# 7_Peripherals.net
KiCad netlist of a schematic drawn in Altium Designer
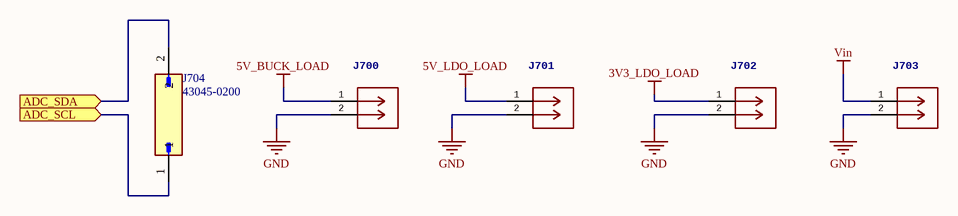
[diagram p0: 7_Peripherals.SchDoc]

(export (version "E")
  (design (tool "Eeschema 10.0.6"))
  (components
    (comp (ref "J700")
      (value "05325-90229")
      (footprint "MOLEX_532590229")
      (description "Molex Mighty-SPOX 2POS")
      (fields (field (name "MANUFACTURER") "Molex") (field (name "PARTNUMBER") "532590229"))
      (libsource (lib "Connectors") (part "0532590229"))
    )
    (comp (ref "J701")
      (value "05325-90229")
      (footprint "MOLEX_532590229")
      (description "Molex Mighty-SPOX 2POS")
      (fields (field (name "MANUFACTURER") "Molex") (field (name "PARTNUMBER") "532590229"))
      (libsource (lib "Connectors") (part "0532590229"))
    )
    (comp (ref "J702")
      (value "05325-90229")
      (footprint "MOLEX_532590229")
      (description "Molex Mighty-SPOX 2POS")
      (fields (field (name "MANUFACTURER") "Molex") (field (name "PARTNUMBER") "532590229"))
      (libsource (lib "Connectors") (part "0532590229"))
    )
    (comp (ref "J703")
      (value "05325-90229")
      (footprint "MOLEX_532590229")
      (description "Molex Mighty-SPOX 2POS")
      (fields (field (name "MANUFACTURER") "Molex") (field (name "PARTNUMBER") "532590229"))
      (libsource (lib "Connectors") (part "0532590229"))
    )
    (comp (ref "J704")
      (value "43045-0200")
      (footprint "MOLEX_43045-0200")
      (description "Molex Microfit 2POS")
      (fields (field (name "MF") "Molex") (field (name "DIGI-KEY_PART_NUMBER") "WM1813-ND"))
      (libsource (lib "Connectors") (part "43045-0200"))
    )
  )
  (nets
    (net (code "1") (name "/ADC_SCL") (class "Default")
      (node (ref "J704") (pin "1") (pinfunction "1_1") (pintype "passive"))
    )
    (net (code "2") (name "/ADC_SDA") (class "Default")
      (node (ref "J704") (pin "2") (pinfunction "2_2") (pintype "passive"))
    )
    (net (code "3") (name "3V3_LDO_LOAD") (class "Default")
      (node (ref "J702") (pin "1") (pinfunction "1_1") (pintype "passive"))
    )
    (net (code "4") (name "5V_BUCK_LOAD") (class "Default")
      (node (ref "J700") (pin "1") (pinfunction "1_1") (pintype "passive"))
    )
    (net (code "5") (name "5V_LDO_LOAD") (class "Default")
      (node (ref "J701") (pin "1") (pinfunction "1_1") (pintype "passive"))
    )
    (net (code "6") (name "GND") (class "Default")
      (node (ref "J700") (pin "2") (pinfunction "2_2") (pintype "passive"))
      (node (ref "J701") (pin "2") (pinfunction "2_2") (pintype "passive"))
      (node (ref "J702") (pin "2") (pinfunction "2_2") (pintype "passive"))
      (node (ref "J703") (pin "2") (pinfunction "2_2") (pintype "passive"))
    )
    (net (code "7") (name "Vin") (class "Default")
      (node (ref "J703") (pin "1") (pinfunction "1_1") (pintype "passive"))
    )
  )
)
